# BLE.net
KiCad netlist of a schematic drawn in Altium Designer
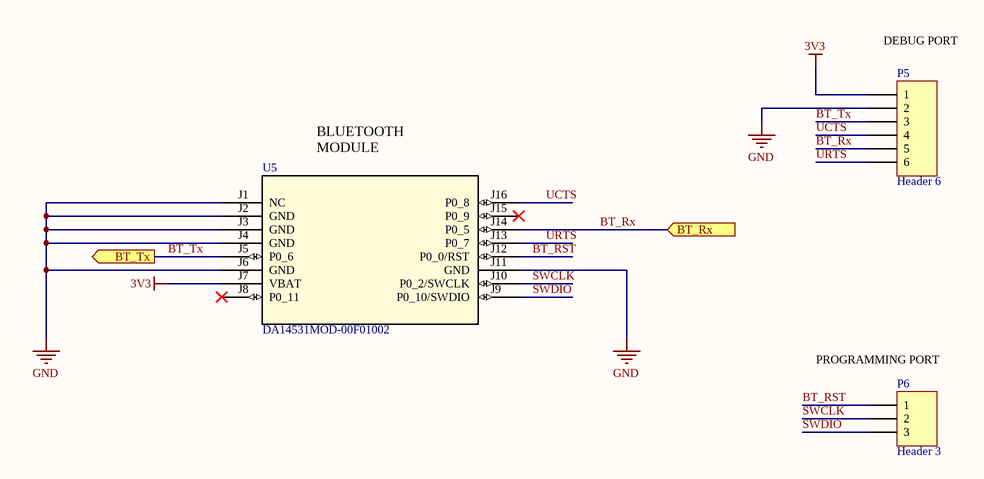
[diagram p0: BLE.SchDoc]

(export (version "E")
  (design (tool "Eeschema 10.0.6"))
  (components
    (comp (ref "P5")
      (value "Header 6")
      (footprint "HDR1X6")
      (description "Header, 6-Pin")
      (fields (field (name "PUBLISHER") "Altium Limited"))
      (libsource (lib "Miscellaneous Connectors") (part "Header 6"))
    )
    (comp (ref "P6")
      (value "Header 3")
      (footprint "HDR1X3")
      (description "Header, 3-Pin")
      (fields (field (name "PUBLISHER") "Altium Limited"))
      (libsource (lib "Miscellaneous Connectors") (part "Header 3"))
    )
    (comp (ref "U5")
      (value "DA14531MOD-00F01002")
      (footprint "DA14531MOD_REN")
      (description "No Description Available")
      (libsource (lib "DA14531MOD-00F01002") (part "DA14531MOD-00F01002"))
    )
  )
  (nets
    (net (code "1") (name "/BT_RST") (class "Default")
      (node (ref "P6") (pin "1") (pinfunction "1_1") (pintype "passive"))
      (node (ref "U5") (pin "J12") (pinfunction "P0_0/RST_J12") (pintype "bidirectional"))
    )
    (net (code "2") (name "/BT_Rx") (class "Default")
      (node (ref "P5") (pin "5") (pinfunction "5_5") (pintype "passive"))
      (node (ref "U5") (pin "J14") (pinfunction "P0_5_J14") (pintype "bidirectional"))
    )
    (net (code "3") (name "/BT_Tx") (class "Default")
      (node (ref "P5") (pin "3") (pinfunction "3_3") (pintype "passive"))
      (node (ref "U5") (pin "J5") (pinfunction "P0_6_J5") (pintype "bidirectional"))
    )
    (net (code "4") (name "/SWCLK") (class "Default")
      (node (ref "P6") (pin "2") (pinfunction "2_2") (pintype "passive"))
      (node (ref "U5") (pin "J10") (pinfunction "P0_2/SWCLK_J10") (pintype "bidirectional"))
    )
    (net (code "5") (name "/SWDIO") (class "Default")
      (node (ref "P6") (pin "3") (pinfunction "3_3") (pintype "passive"))
      (node (ref "U5") (pin "J9") (pinfunction "P0_10/SWDIO_J9") (pintype "bidirectional"))
    )
    (net (code "6") (name "/UCTS") (class "Default")
      (node (ref "P5") (pin "4") (pinfunction "4_4") (pintype "passive"))
      (node (ref "U5") (pin "J16") (pinfunction "P0_8_J16") (pintype "bidirectional"))
    )
    (net (code "7") (name "/URTS") (class "Default")
      (node (ref "P5") (pin "6") (pinfunction "6_6") (pintype "passive"))
      (node (ref "U5") (pin "J13") (pinfunction "P0_7_J13") (pintype "bidirectional"))
    )
    (net (code "8") (name "3V3") (class "Default")
      (node (ref "P5") (pin "1") (pinfunction "1_1") (pintype "passive"))
      (node (ref "U5") (pin "J7") (pinfunction "VBAT_J7") (pintype "power_in"))
    )
    (net (code "9") (name "GND") (class "Default")
      (node (ref "P5") (pin "2") (pinfunction "2_2") (pintype "passive"))
      (node (ref "U5") (pin "J1") (pinfunction "NC_J1") (pintype "passive"))
      (node (ref "U5") (pin "J11") (pinfunction "GND_J11") (pintype "power_in"))
      (node (ref "U5") (pin "J2") (pinfunction "GND_J2") (pintype "power_in"))
      (node (ref "U5") (pin "J3") (pinfunction "GND_J3") (pintype "power_in"))
      (node (ref "U5") (pin "J4") (pinfunction "GND_J4") (pintype "power_in"))
      (node (ref "U5") (pin "J6") (pinfunction "GND_J6") (pintype "power_in"))
    )
    (net (code "10") (name "unconnected-(U5-P0_9-PadJ15)") (class "Default")
      (node (ref "U5") (pin "J15") (pinfunction "P0_9_J15") (pintype "bidirectional+no_connect"))
    )
    (net (code "11") (name "unconnected-(U5-P0_11-PadJ8)") (class "Default")
      (node (ref "U5") (pin "J8") (pinfunction "P0_11_J8") (pintype "bidirectional+no_connect"))
    )
  )
)
